# CPU_final_rev02.net
KiCad netlist of a schematic drawn in EAGLE
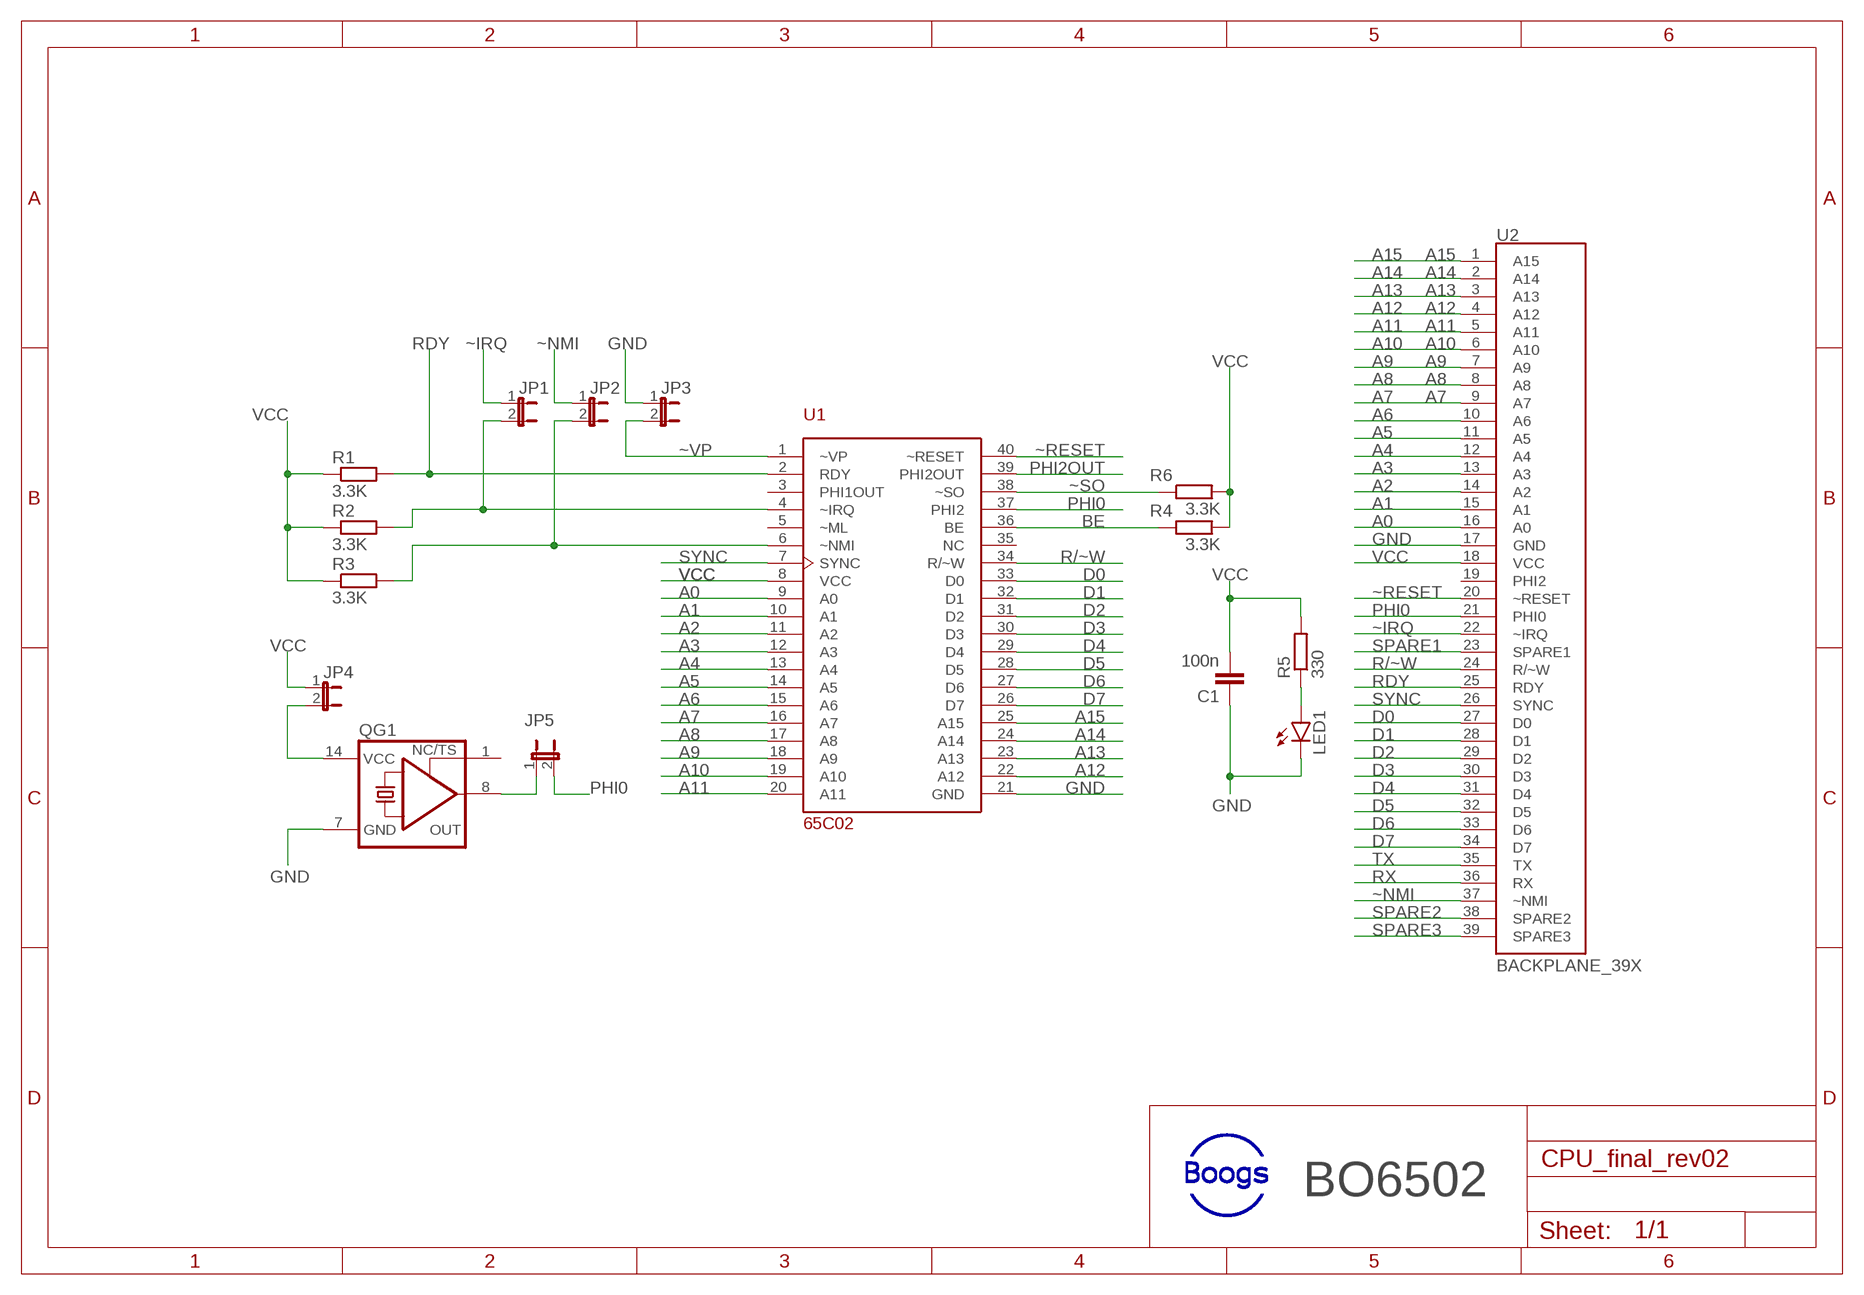
[diagram p0: schematic, sheet 1]

(export (version "E")
  (design (tool "Eeschema 10.0.6"))
  (components
    (comp (ref "C1")
      (value "100n")
      (footprint "eagle-import:C025-025X050")
      (libsource (lib "eagle-import") (part "C-EU025-025X050"))
    )
    (comp (ref "JP1")
      (value "JP1E")
      (footprint "eagle-import:JP1")
      (libsource (lib "eagle-import") (part "JP1E"))
    )
    (comp (ref "JP2")
      (value "JP1E")
      (footprint "eagle-import:JP1")
      (libsource (lib "eagle-import") (part "JP1E"))
    )
    (comp (ref "JP3")
      (value "JP1E")
      (footprint "eagle-import:JP1")
      (libsource (lib "eagle-import") (part "JP1E"))
    )
    (comp (ref "JP4")
      (value "JP1E")
      (footprint "eagle-import:JP1")
      (libsource (lib "eagle-import") (part "JP1E"))
    )
    (comp (ref "JP5")
      (value "JP1E")
      (footprint "eagle-import:JP1")
      (libsource (lib "eagle-import") (part "JP1E"))
    )
    (comp (ref "LED1")
      (value "LED5MM")
      (footprint "eagle-import:LED5MM")
      (libsource (lib "eagle-import") (part "LED5MM"))
    )
    (comp (ref "QG1")
      (value "XO-14")
      (footprint "eagle-import:DIL14S")
      (libsource (lib "eagle-import") (part "XO-14"))
    )
    (comp (ref "R1")
      (value "3.3K")
      (footprint "eagle-import:0207_10")
      (libsource (lib "eagle-import") (part "R-EU_0207/10"))
    )
    (comp (ref "R2")
      (value "3.3K")
      (footprint "eagle-import:0207_10")
      (libsource (lib "eagle-import") (part "R-EU_0207/10"))
    )
    (comp (ref "R3")
      (value "3.3K")
      (footprint "eagle-import:0207_10")
      (libsource (lib "eagle-import") (part "R-EU_0207/10"))
    )
    (comp (ref "R4")
      (value "3.3K")
      (footprint "eagle-import:0207_10")
      (libsource (lib "eagle-import") (part "R-EU_0207/10"))
    )
    (comp (ref "R5")
      (value "330")
      (footprint "eagle-import:0207_10")
      (libsource (lib "eagle-import") (part "R-EU_0207/10"))
    )
    (comp (ref "R6")
      (value "3.3K")
      (footprint "eagle-import:0207_10")
      (libsource (lib "eagle-import") (part "R-EU_0207/10"))
    )
    (comp (ref "U1")
      (value "65C02")
      (footprint "eagle-import:DIL40")
      (libsource (lib "eagle-import") (part "65C02"))
    )
    (comp (ref "U2")
      (value "BACKPLANE_39X")
      (footprint "eagle-import:BP_39X")
      (fields
        (field (name "PIN_1") "A15")
        (field (name "PIN_2") "A14")
        (field (name "PIN_3") "A13")
        (field (name "PIN_4") "A12")
        (field (name "PIN_5") "A11")
        (field (name "PIN_6") "A10")
        (field (name "PIN_7") "A9")
        (field (name "PIN_8") "A8")
        (field (name "PIN_9") "A7")
      )
      (libsource (lib "eagle-import") (part "BACKPLANE_39X"))
    )
  )
  (nets
    (net (code "1") (name "/A0") (class "Default")
      (node (ref "U1") (pin "9") (pinfunction "A0_9") (pintype "bidirectional"))
      (node (ref "U2") (pin "16") (pinfunction "A0_16") (pintype "bidirectional"))
    )
    (net (code "2") (name "/A1") (class "Default")
      (node (ref "U1") (pin "10") (pinfunction "A1_10") (pintype "bidirectional"))
      (node (ref "U2") (pin "15") (pinfunction "A1_15") (pintype "bidirectional"))
    )
    (net (code "3") (name "/A2") (class "Default")
      (node (ref "U1") (pin "11") (pinfunction "A2_11") (pintype "bidirectional"))
      (node (ref "U2") (pin "14") (pinfunction "A2_14") (pintype "bidirectional"))
    )
    (net (code "4") (name "/A3") (class "Default")
      (node (ref "U1") (pin "12") (pinfunction "A3_12") (pintype "bidirectional"))
      (node (ref "U2") (pin "13") (pinfunction "A3_13") (pintype "bidirectional"))
    )
    (net (code "5") (name "/A4") (class "Default")
      (node (ref "U1") (pin "13") (pinfunction "A4_13") (pintype "bidirectional"))
      (node (ref "U2") (pin "12") (pinfunction "A4_12") (pintype "bidirectional"))
    )
    (net (code "6") (name "/A5") (class "Default")
      (node (ref "U1") (pin "14") (pinfunction "A5_14") (pintype "bidirectional"))
      (node (ref "U2") (pin "11") (pinfunction "A5_11") (pintype "bidirectional"))
    )
    (net (code "7") (name "/A6") (class "Default")
      (node (ref "U1") (pin "15") (pinfunction "A6_15") (pintype "bidirectional"))
      (node (ref "U2") (pin "10") (pinfunction "A6_10") (pintype "bidirectional"))
    )
    (net (code "8") (name "/A7") (class "Default")
      (node (ref "U1") (pin "16") (pinfunction "A7_16") (pintype "bidirectional"))
      (node (ref "U2") (pin "9") (pinfunction "A7_9") (pintype "bidirectional"))
    )
    (net (code "9") (name "/A8") (class "Default")
      (node (ref "U1") (pin "17") (pinfunction "A8_17") (pintype "bidirectional"))
      (node (ref "U2") (pin "8") (pinfunction "A8_8") (pintype "bidirectional"))
    )
    (net (code "10") (name "/A9") (class "Default")
      (node (ref "U1") (pin "18") (pinfunction "A9_18") (pintype "bidirectional"))
      (node (ref "U2") (pin "7") (pinfunction "A9_7") (pintype "bidirectional"))
    )
    (net (code "11") (name "/A10") (class "Default")
      (node (ref "U1") (pin "19") (pinfunction "A10_19") (pintype "bidirectional"))
      (node (ref "U2") (pin "6") (pinfunction "A10_6") (pintype "bidirectional"))
    )
    (net (code "12") (name "/A11") (class "Default")
      (node (ref "U1") (pin "20") (pinfunction "A11_20") (pintype "bidirectional"))
      (node (ref "U2") (pin "5") (pinfunction "A11_5") (pintype "bidirectional"))
    )
    (net (code "13") (name "/A12") (class "Default")
      (node (ref "U1") (pin "22") (pinfunction "A12_22") (pintype "bidirectional"))
      (node (ref "U2") (pin "4") (pinfunction "A12_4") (pintype "bidirectional"))
    )
    (net (code "14") (name "/A13") (class "Default")
      (node (ref "U1") (pin "23") (pinfunction "A13_23") (pintype "bidirectional"))
      (node (ref "U2") (pin "3") (pinfunction "A13_3") (pintype "bidirectional"))
    )
    (net (code "15") (name "/A14") (class "Default")
      (node (ref "U1") (pin "24") (pinfunction "A14_24") (pintype "bidirectional"))
      (node (ref "U2") (pin "2") (pinfunction "A14_2") (pintype "bidirectional"))
    )
    (net (code "16") (name "/A15") (class "Default")
      (node (ref "U1") (pin "25") (pinfunction "A15_25") (pintype "bidirectional"))
      (node (ref "U2") (pin "1") (pinfunction "A15_1") (pintype "bidirectional"))
    )
    (net (code "17") (name "/BE") (class "Default")
      (node (ref "R4") (pin "1") (pinfunction "1_1") (pintype "passive"))
      (node (ref "U1") (pin "36") (pinfunction "BE_36") (pintype "bidirectional"))
    )
    (net (code "18") (name "/D0") (class "Default")
      (node (ref "U1") (pin "33") (pinfunction "D0_33") (pintype "bidirectional"))
      (node (ref "U2") (pin "27") (pinfunction "D0_27") (pintype "bidirectional"))
    )
    (net (code "19") (name "/D1") (class "Default")
      (node (ref "U1") (pin "32") (pinfunction "D1_32") (pintype "bidirectional"))
      (node (ref "U2") (pin "28") (pinfunction "D1_28") (pintype "bidirectional"))
    )
    (net (code "20") (name "/D2") (class "Default")
      (node (ref "U1") (pin "31") (pinfunction "D2_31") (pintype "bidirectional"))
      (node (ref "U2") (pin "29") (pinfunction "D2_29") (pintype "bidirectional"))
    )
    (net (code "21") (name "/D3") (class "Default")
      (node (ref "U1") (pin "30") (pinfunction "D3_30") (pintype "bidirectional"))
      (node (ref "U2") (pin "30") (pinfunction "D3_30") (pintype "bidirectional"))
    )
    (net (code "22") (name "/D4") (class "Default")
      (node (ref "U1") (pin "29") (pinfunction "D4_29") (pintype "bidirectional"))
      (node (ref "U2") (pin "31") (pinfunction "D4_31") (pintype "bidirectional"))
    )
    (net (code "23") (name "/D5") (class "Default")
      (node (ref "U1") (pin "28") (pinfunction "D5_28") (pintype "bidirectional"))
      (node (ref "U2") (pin "32") (pinfunction "D5_32") (pintype "bidirectional"))
    )
    (net (code "24") (name "/D6") (class "Default")
      (node (ref "U1") (pin "27") (pinfunction "D6_27") (pintype "bidirectional"))
      (node (ref "U2") (pin "33") (pinfunction "D6_33") (pintype "bidirectional"))
    )
    (net (code "25") (name "/D7") (class "Default")
      (node (ref "U1") (pin "26") (pinfunction "D7_26") (pintype "bidirectional"))
      (node (ref "U2") (pin "34") (pinfunction "D7_34") (pintype "bidirectional"))
    )
    (net (code "26") (name "/GND") (class "Default")
      (node (ref "C1") (pin "1") (pinfunction "1_1") (pintype "passive"))
      (node (ref "JP3") (pin "1") (pinfunction "1_1") (pintype "passive"))
      (node (ref "LED1") (pin "K") (pinfunction "C_K") (pintype "passive"))
      (node (ref "QG1") (pin "7") (pinfunction "GND_7") (pintype "power_in"))
      (node (ref "U1") (pin "21") (pinfunction "GND_21") (pintype "power_in"))
      (node (ref "U2") (pin "17") (pinfunction "GND_17") (pintype "bidirectional"))
    )
    (net (code "27") (name "/PHI0") (class "Default")
      (node (ref "JP5") (pin "2") (pinfunction "2_2") (pintype "passive"))
      (node (ref "U1") (pin "37") (pinfunction "PHI2_37") (pintype "bidirectional"))
      (node (ref "U2") (pin "21") (pinfunction "PHI0_21") (pintype "bidirectional"))
    )
    (net (code "28") (name "/PHI2OUT") (class "Default")
      (node (ref "U1") (pin "39") (pinfunction "PHI2OUT_39") (pintype "bidirectional"))
    )
    (net (code "29") (name "/RDY") (class "Default")
      (node (ref "R1") (pin "2") (pinfunction "2_2") (pintype "passive"))
      (node (ref "U1") (pin "2") (pinfunction "RDY_2") (pintype "bidirectional"))
      (node (ref "U2") (pin "25") (pinfunction "RDY_25") (pintype "bidirectional"))
    )
    (net (code "30") (name "/RX") (class "Default")
      (node (ref "U2") (pin "36") (pinfunction "RX_36") (pintype "bidirectional"))
    )
    (net (code "31") (name "/R{slash}~{W}") (class "Default")
      (node (ref "U1") (pin "34") (pinfunction "R/~{W}_34") (pintype "bidirectional"))
      (node (ref "U2") (pin "24") (pinfunction "R/~{W}_24") (pintype "bidirectional"))
    )
    (net (code "32") (name "/SPARE1") (class "Default")
      (node (ref "U2") (pin "23") (pinfunction "SPARE1_23") (pintype "bidirectional"))
    )
    (net (code "33") (name "/SPARE2") (class "Default")
      (node (ref "U2") (pin "38") (pinfunction "SPARE2_38") (pintype "bidirectional"))
    )
    (net (code "34") (name "/SPARE3") (class "Default")
      (node (ref "U2") (pin "39") (pinfunction "SPARE3_39") (pintype "bidirectional"))
    )
    (net (code "35") (name "/SYNC") (class "Default")
      (node (ref "U1") (pin "7") (pinfunction "SYNC_7") (pintype "input"))
      (node (ref "U2") (pin "26") (pinfunction "SYNC_26") (pintype "bidirectional"))
    )
    (net (code "36") (name "/TX") (class "Default")
      (node (ref "U2") (pin "35") (pinfunction "TX_35") (pintype "bidirectional"))
    )
    (net (code "37") (name "/VCC") (class "Default")
      (node (ref "C1") (pin "2") (pinfunction "2_2") (pintype "passive"))
      (node (ref "JP4") (pin "1") (pinfunction "1_1") (pintype "passive"))
      (node (ref "R1") (pin "1") (pinfunction "1_1") (pintype "passive"))
      (node (ref "R2") (pin "1") (pinfunction "1_1") (pintype "passive"))
      (node (ref "R3") (pin "1") (pinfunction "1_1") (pintype "passive"))
      (node (ref "R4") (pin "2") (pinfunction "2_2") (pintype "passive"))
      (node (ref "R5") (pin "2") (pinfunction "2_2") (pintype "passive"))
      (node (ref "R6") (pin "2") (pinfunction "2_2") (pintype "passive"))
      (node (ref "U1") (pin "8") (pinfunction "VCC_8") (pintype "power_in"))
      (node (ref "U2") (pin "18") (pinfunction "VCC_18") (pintype "bidirectional"))
    )
    (net (code "38") (name "/~{IRQ}") (class "Default")
      (node (ref "JP1") (pin "1") (pinfunction "1_1") (pintype "passive"))
      (node (ref "U2") (pin "22") (pinfunction "~{IRQ}_22") (pintype "bidirectional"))
    )
    (net (code "39") (name "/~{NMI}") (class "Default")
      (node (ref "JP2") (pin "1") (pinfunction "1_1") (pintype "passive"))
      (node (ref "U2") (pin "37") (pinfunction "~{NMI}_37") (pintype "bidirectional"))
    )
    (net (code "40") (name "/~{RESET}") (class "Default")
      (node (ref "U1") (pin "40") (pinfunction "~{RESET}_40") (pintype "bidirectional"))
      (node (ref "U2") (pin "20") (pinfunction "~{RESET}_20") (pintype "bidirectional"))
    )
    (net (code "41") (name "/~{SO}") (class "Default")
      (node (ref "R6") (pin "1") (pinfunction "1_1") (pintype "passive"))
      (node (ref "U1") (pin "38") (pinfunction "~{SO}_38") (pintype "bidirectional"))
    )
    (net (code "42") (name "/~{VP}") (class "Default")
      (node (ref "JP3") (pin "2") (pinfunction "2_2") (pintype "passive"))
      (node (ref "U1") (pin "1") (pinfunction "~{VP}_1") (pintype "bidirectional"))
    )
    (net (code "43") (name "Net-(LED1-PadA)") (class "Default")
      (node (ref "LED1") (pin "A") (pinfunction "A_A") (pintype "passive"))
      (node (ref "R5") (pin "1") (pinfunction "1_1") (pintype "passive"))
    )
    (net (code "44") (name "Net-(QG1-OUT)") (class "Default")
      (node (ref "JP5") (pin "1") (pinfunction "1_1") (pintype "passive"))
      (node (ref "QG1") (pin "8") (pinfunction "OUT_8") (pintype "output"))
    )
    (net (code "45") (name "Net-(QG1-VCC)") (class "Default")
      (node (ref "JP4") (pin "2") (pinfunction "2_2") (pintype "passive"))
      (node (ref "QG1") (pin "14") (pinfunction "VCC_14") (pintype "power_in"))
    )
    (net (code "46") (name "Net-(U1-~{IRQ})") (class "Default")
      (node (ref "JP1") (pin "2") (pinfunction "2_2") (pintype "passive"))
      (node (ref "R2") (pin "2") (pinfunction "2_2") (pintype "passive"))
      (node (ref "U1") (pin "4") (pinfunction "~{IRQ}_4") (pintype "bidirectional"))
    )
    (net (code "47") (name "Net-(U1-~{NMI})") (class "Default")
      (node (ref "JP2") (pin "2") (pinfunction "2_2") (pintype "passive"))
      (node (ref "R3") (pin "2") (pinfunction "2_2") (pintype "passive"))
      (node (ref "U1") (pin "6") (pinfunction "~{NMI}_6") (pintype "bidirectional"))
    )
    (net (code "48") (name "unconnected-(QG1-TS-Pad1)") (class "Default")
      (node (ref "QG1") (pin "1") (pinfunction "TS_1") (pintype "passive"))
    )
    (net (code "49") (name "unconnected-(U1-NC-Pad35)") (class "Default")
      (node (ref "U1") (pin "35") (pinfunction "NC_35") (pintype "bidirectional"))
    )
    (net (code "50") (name "unconnected-(U1-PHI1OUT-Pad3)") (class "Default")
      (node (ref "U1") (pin "3") (pinfunction "PHI1OUT_3") (pintype "bidirectional"))
    )
    (net (code "51") (name "unconnected-(U1-~{ML}-Pad5)") (class "Default")
      (node (ref "U1") (pin "5") (pinfunction "~{ML}_5") (pintype "bidirectional"))
    )
    (net (code "52") (name "unconnected-(U2-PHI2-Pad19)") (class "Default")
      (node (ref "U2") (pin "19") (pinfunction "PHI2_19") (pintype "bidirectional"))
    )
  )
)
